# OSC4ReTHM.net
KiCad netlist of a schematic drawn in EAGLE
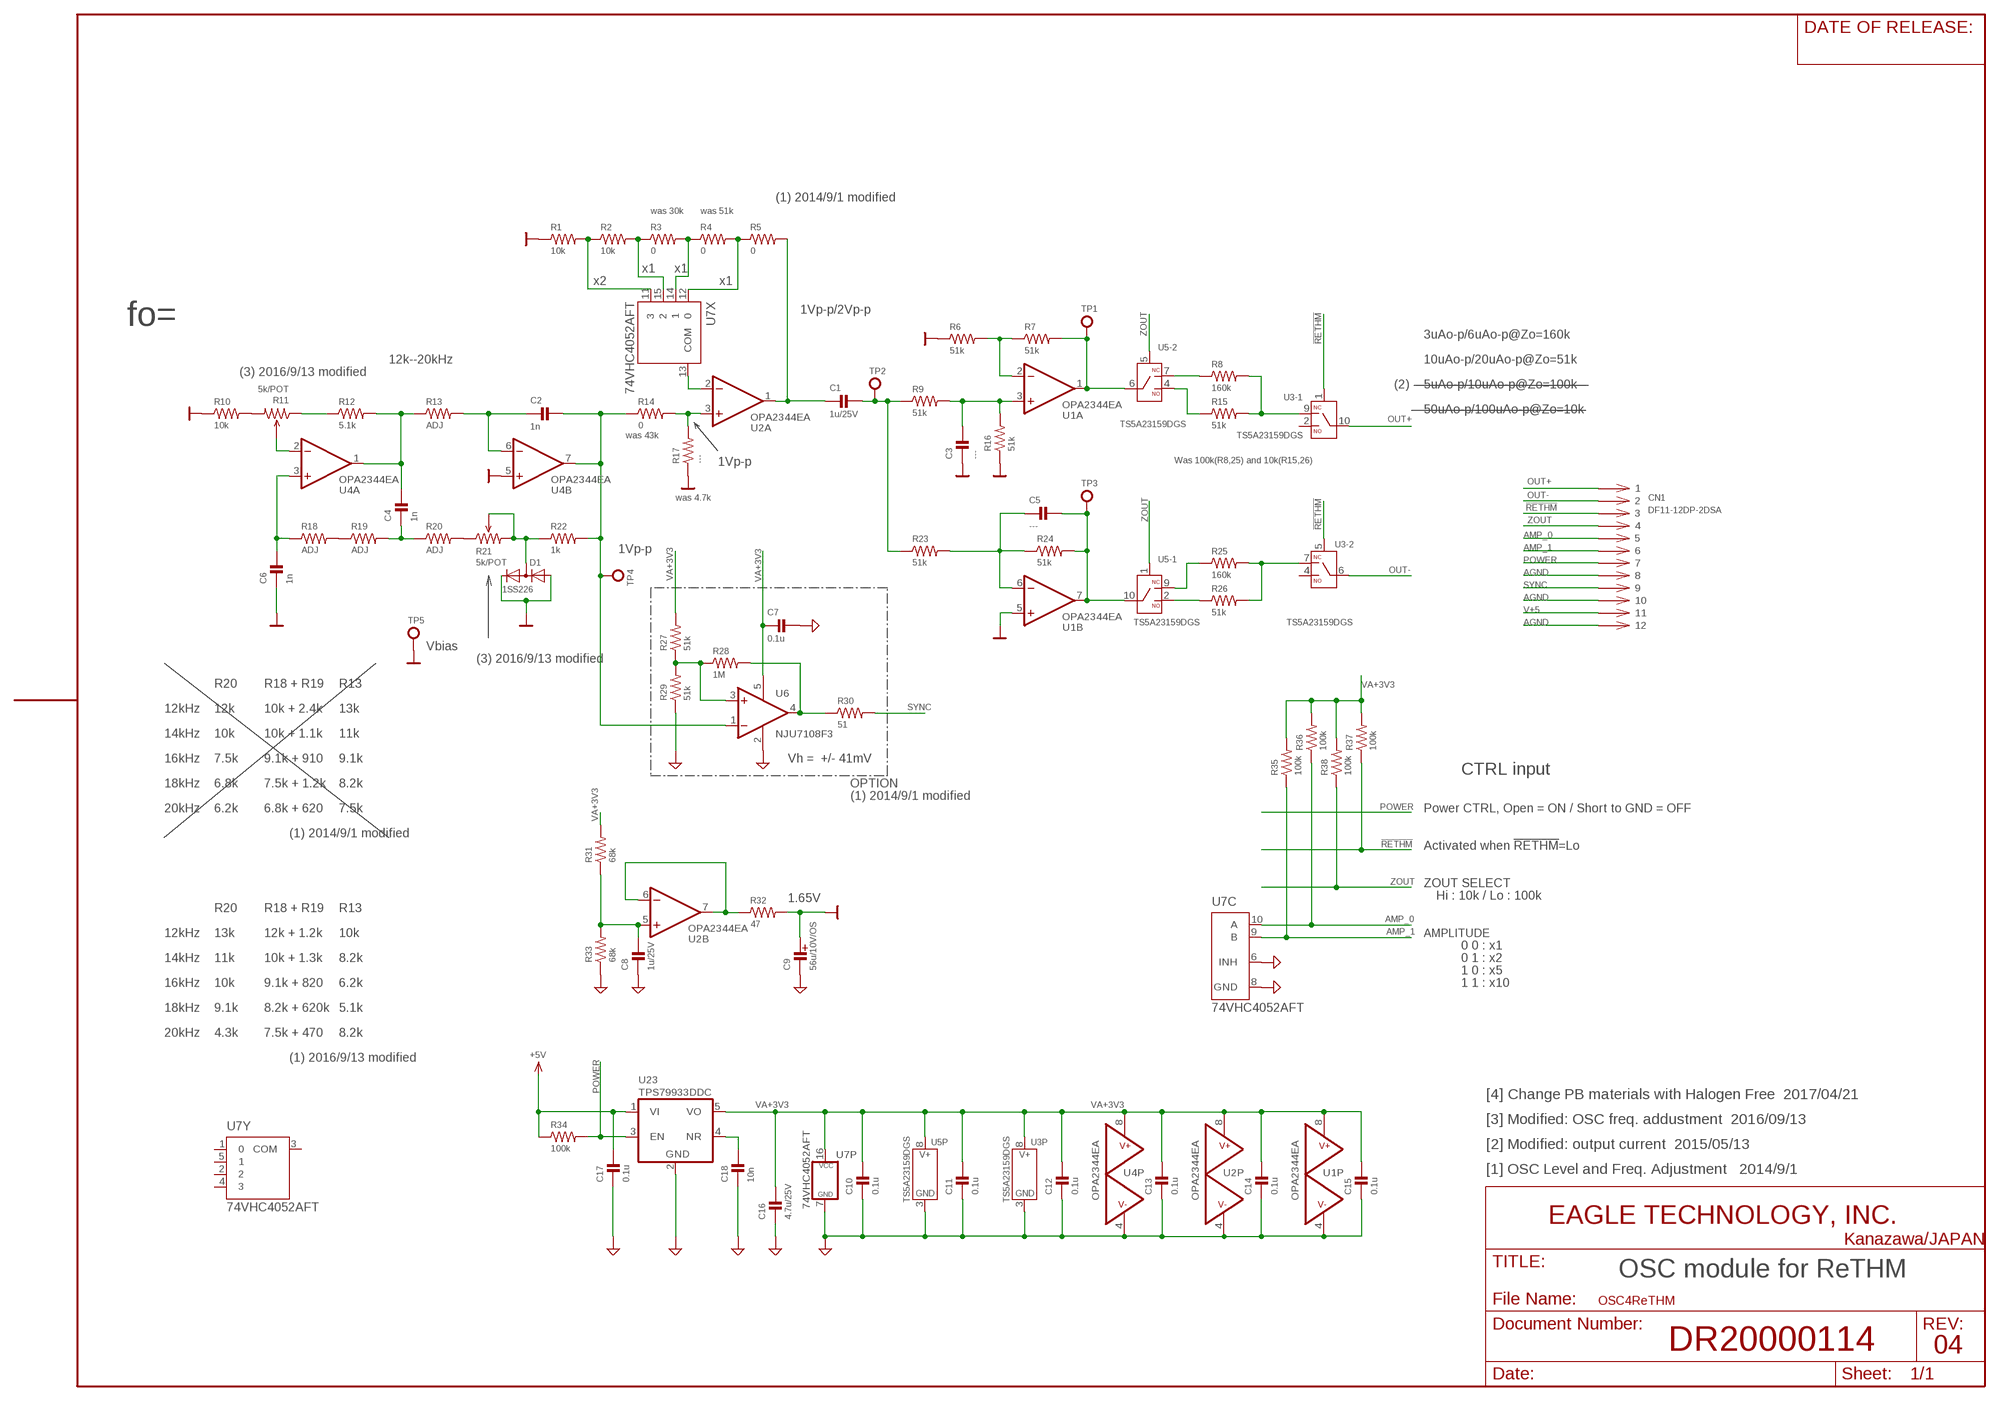
[diagram p0: schematic, sheet 1]

(export (version "E")
  (design (tool "Eeschema 10.0.6"))
  (components
    (comp (ref "C1")
      (value "1u/25V")
      (footprint "eagle-import:CM1608")
      (libsource (lib "eagle-import") (part "CSMD1.6X0.8MM"))
    )
    (comp (ref "C2")
      (value "1n")
      (footprint "eagle-import:CM2012")
      (libsource (lib "eagle-import") (part "CSMD2.0X1.2MM"))
    )
    (comp (ref "C3")
      (value "---")
      (footprint "eagle-import:CM2012")
      (libsource (lib "eagle-import") (part "CSMD2.0X1.2MM"))
    )
    (comp (ref "C4")
      (value "1n")
      (footprint "eagle-import:CM2012")
      (libsource (lib "eagle-import") (part "CSMD2.0X1.2MM"))
    )
    (comp (ref "C5")
      (value "---")
      (footprint "eagle-import:CM2012")
      (libsource (lib "eagle-import") (part "CSMD2.0X1.2MM"))
    )
    (comp (ref "C6")
      (value "1n")
      (footprint "eagle-import:CM2012")
      (libsource (lib "eagle-import") (part "CSMD2.0X1.2MM"))
    )
    (comp (ref "C7")
      (value "0.1u")
      (footprint "eagle-import:CM1608")
      (libsource (lib "eagle-import") (part "CSMD1.6X0.8MM"))
    )
    (comp (ref "C8")
      (value "1u/25V")
      (footprint "eagle-import:CM1608")
      (libsource (lib "eagle-import") (part "CSMD1.6X0.8MM"))
    )
    (comp (ref "C9")
      (value "56u/10V/OS")
      (footprint "eagle-import:PHI_6.3")
      (libsource (lib "eagle-import") (part "C_POL6.3-2.5MM"))
    )
    (comp (ref "C10")
      (value "0.1u")
      (footprint "eagle-import:CM1608")
      (libsource (lib "eagle-import") (part "CSMD1.6X0.8MM"))
    )
    (comp (ref "C11")
      (value "0.1u")
      (footprint "eagle-import:CM1608")
      (libsource (lib "eagle-import") (part "CSMD1.6X0.8MM"))
    )
    (comp (ref "C12")
      (value "0.1u")
      (footprint "eagle-import:CM1608")
      (libsource (lib "eagle-import") (part "CSMD1.6X0.8MM"))
    )
    (comp (ref "C13")
      (value "0.1u")
      (footprint "eagle-import:CM1608")
      (libsource (lib "eagle-import") (part "CSMD1.6X0.8MM"))
    )
    (comp (ref "C14")
      (value "0.1u")
      (footprint "eagle-import:CM1608")
      (libsource (lib "eagle-import") (part "CSMD1.6X0.8MM"))
    )
    (comp (ref "C15")
      (value "0.1u")
      (footprint "eagle-import:CM1608")
      (libsource (lib "eagle-import") (part "CSMD1.6X0.8MM"))
    )
    (comp (ref "C16")
      (value "4.7u/25V")
      (footprint "eagle-import:CM2012")
      (libsource (lib "eagle-import") (part "CSMD2.0X1.2MM"))
    )
    (comp (ref "C17")
      (value "0.1u")
      (footprint "eagle-import:CM1608")
      (libsource (lib "eagle-import") (part "CSMD1.6X0.8MM"))
    )
    (comp (ref "C18")
      (value "10n")
      (footprint "eagle-import:CM2012")
      (libsource (lib "eagle-import") (part "CSMD2.0X1.2MM"))
    )
    (comp (ref "CN1")
      (value "DF11-12DP-2DSA")
      (footprint "eagle-import:DF11-12DP-2DSA")
      (libsource (lib "eagle-import") (part "DF11-12DP-2DSA"))
    )
    (comp (ref "D1")
      (value "1SS226")
      (footprint "eagle-import:SOT23")
      (libsource (lib "eagle-import") (part "1SS226"))
    )
    (comp (ref "R1")
      (value "10k")
      (footprint "eagle-import:RM1608")
      (libsource (lib "eagle-import") (part "RSMD1.6X0.8MM"))
    )
    (comp (ref "R2")
      (value "10k")
      (footprint "eagle-import:RM1608")
      (libsource (lib "eagle-import") (part "RSMD1.6X0.8MM"))
    )
    (comp (ref "R3")
      (value "0")
      (footprint "eagle-import:RM1608")
      (libsource (lib "eagle-import") (part "RSMD1.6X0.8MM"))
    )
    (comp (ref "R4")
      (value "0")
      (footprint "eagle-import:RM1608")
      (libsource (lib "eagle-import") (part "RSMD1.6X0.8MM"))
    )
    (comp (ref "R5")
      (value "0")
      (footprint "eagle-import:RM1608")
      (libsource (lib "eagle-import") (part "RSMD1.6X0.8MM"))
    )
    (comp (ref "R6")
      (value "51k")
      (footprint "eagle-import:RM1608")
      (libsource (lib "eagle-import") (part "RSMD1.6X0.8MM"))
    )
    (comp (ref "R7")
      (value "51k")
      (footprint "eagle-import:RM1608")
      (libsource (lib "eagle-import") (part "RSMD1.6X0.8MM"))
    )
    (comp (ref "R8")
      (value "160k")
      (footprint "eagle-import:RM1608")
      (libsource (lib "eagle-import") (part "RSMD1.6X0.8MM"))
    )
    (comp (ref "R9")
      (value "51k")
      (footprint "eagle-import:RM1608")
      (libsource (lib "eagle-import") (part "RSMD1.6X0.8MM"))
    )
    (comp (ref "R10")
      (value "10k")
      (footprint "eagle-import:RM1608")
      (libsource (lib "eagle-import") (part "RSMD1.6X0.8MM"))
    )
    (comp (ref "R11")
      (value "5k/POT")
      (footprint "eagle-import:CT-6")
      (libsource (lib "eagle-import") (part "R_POT"))
    )
    (comp (ref "R12")
      (value "5.1k")
      (footprint "eagle-import:RM1608")
      (libsource (lib "eagle-import") (part "RSMD1.6X0.8MM"))
    )
    (comp (ref "R13")
      (value "ADJ")
      (footprint "eagle-import:RM1608")
      (libsource (lib "eagle-import") (part "RSMD1.6X0.8MM"))
    )
    (comp (ref "R14")
      (value "0")
      (footprint "eagle-import:RM1608")
      (libsource (lib "eagle-import") (part "RSMD1.6X0.8MM"))
    )
    (comp (ref "R15")
      (value "51k")
      (footprint "eagle-import:RM1608")
      (libsource (lib "eagle-import") (part "RSMD1.6X0.8MM"))
    )
    (comp (ref "R16")
      (value "51k")
      (footprint "eagle-import:RM1608")
      (libsource (lib "eagle-import") (part "RSMD1.6X0.8MM"))
    )
    (comp (ref "R17")
      (value "---")
      (footprint "eagle-import:RM1608")
      (libsource (lib "eagle-import") (part "RSMD1.6X0.8MM"))
    )
    (comp (ref "R18")
      (value "ADJ")
      (footprint "eagle-import:RM1608")
      (libsource (lib "eagle-import") (part "RSMD1.6X0.8MM"))
    )
    (comp (ref "R19")
      (value "ADJ")
      (footprint "eagle-import:RM1608")
      (libsource (lib "eagle-import") (part "RSMD1.6X0.8MM"))
    )
    (comp (ref "R20")
      (value "ADJ")
      (footprint "eagle-import:RM1608")
      (libsource (lib "eagle-import") (part "RSMD1.6X0.8MM"))
    )
    (comp (ref "R21")
      (value "5k/POT")
      (footprint "eagle-import:CT-6")
      (libsource (lib "eagle-import") (part "R_POT"))
    )
    (comp (ref "R22")
      (value "1k")
      (footprint "eagle-import:RM1608")
      (libsource (lib "eagle-import") (part "RSMD1.6X0.8MM"))
    )
    (comp (ref "R23")
      (value "51k")
      (footprint "eagle-import:RM1608")
      (libsource (lib "eagle-import") (part "RSMD1.6X0.8MM"))
    )
    (comp (ref "R24")
      (value "51k")
      (footprint "eagle-import:RM1608")
      (libsource (lib "eagle-import") (part "RSMD1.6X0.8MM"))
    )
    (comp (ref "R25")
      (value "160k")
      (footprint "eagle-import:RM1608")
      (libsource (lib "eagle-import") (part "RSMD1.6X0.8MM"))
    )
    (comp (ref "R26")
      (value "51k")
      (footprint "eagle-import:RM1608")
      (libsource (lib "eagle-import") (part "RSMD1.6X0.8MM"))
    )
    (comp (ref "R27")
      (value "51k")
      (footprint "eagle-import:RM1608")
      (libsource (lib "eagle-import") (part "RSMD1.6X0.8MM"))
    )
    (comp (ref "R28")
      (value "1M")
      (footprint "eagle-import:RM1608")
      (libsource (lib "eagle-import") (part "RSMD1.6X0.8MM"))
    )
    (comp (ref "R29")
      (value "51k")
      (footprint "eagle-import:RM1608")
      (libsource (lib "eagle-import") (part "RSMD1.6X0.8MM"))
    )
    (comp (ref "R30")
      (value "51")
      (footprint "eagle-import:RM1608")
      (libsource (lib "eagle-import") (part "RSMD1.6X0.8MM"))
    )
    (comp (ref "R31")
      (value "68k")
      (footprint "eagle-import:RM1608")
      (libsource (lib "eagle-import") (part "RSMD1.6X0.8MM"))
    )
    (comp (ref "R32")
      (value "47")
      (footprint "eagle-import:RM1608")
      (libsource (lib "eagle-import") (part "RSMD1.6X0.8MM"))
    )
    (comp (ref "R33")
      (value "68k")
      (footprint "eagle-import:RM1608")
      (libsource (lib "eagle-import") (part "RSMD1.6X0.8MM"))
    )
    (comp (ref "R34")
      (value "100k")
      (footprint "eagle-import:RM1608")
      (libsource (lib "eagle-import") (part "RSMD1.6X0.8MM"))
    )
    (comp (ref "R35")
      (value "100k")
      (footprint "eagle-import:RM1608")
      (libsource (lib "eagle-import") (part "RSMD1.6X0.8MM"))
    )
    (comp (ref "R36")
      (value "100k")
      (footprint "eagle-import:RM1608")
      (libsource (lib "eagle-import") (part "RSMD1.6X0.8MM"))
    )
    (comp (ref "R37")
      (value "100k")
      (footprint "eagle-import:RM1608")
      (libsource (lib "eagle-import") (part "RSMD1.6X0.8MM"))
    )
    (comp (ref "R38")
      (value "100k")
      (footprint "eagle-import:RM1608")
      (libsource (lib "eagle-import") (part "RSMD1.6X0.8MM"))
    )
    (comp (ref "TP1")
      (value "TP-1PAD")
      (footprint "eagle-import:TP_PAD_1MM")
      (libsource (lib "eagle-import") (part "TP-1PAD"))
    )
    (comp (ref "TP2")
      (value "TP-LC3G")
      (footprint "eagle-import:TP_TH_0R9MM")
      (libsource (lib "eagle-import") (part "TP-LC3G"))
    )
    (comp (ref "TP3")
      (value "TP-1PAD")
      (footprint "eagle-import:TP_PAD_1MM")
      (libsource (lib "eagle-import") (part "TP-1PAD"))
    )
    (comp (ref "TP4")
      (value "TP-LC3G")
      (footprint "eagle-import:TP_TH_0R9MM")
      (libsource (lib "eagle-import") (part "TP-LC3G"))
    )
    (comp (ref "TP5")
      (value "TP-1PAD")
      (footprint "eagle-import:TP_PAD_1MM")
      (libsource (lib "eagle-import") (part "TP-1PAD"))
    )
    (comp (ref "U1")
      (value "OPA2344EA")
      (footprint "eagle-import:MSO8_AEL")
      (libsource (lib "eagle-import") (part "OPA2344DGK"))
    )
    (comp (ref "U2")
      (value "OPA2344EA")
      (footprint "eagle-import:MSO8_AEL")
      (libsource (lib "eagle-import") (part "OPA2344DGK"))
    )
    (comp (ref "U3")
      (value "TS5A23159DGS")
      (footprint "eagle-import:MSOP10")
      (libsource (lib "eagle-import") (part "TS5A23159DGS"))
    )
    (comp (ref "U4")
      (value "OPA2344EA")
      (footprint "eagle-import:MSO8_AEL")
      (libsource (lib "eagle-import") (part "OPA2344DGK"))
    )
    (comp (ref "U5")
      (value "TS5A23159DGS")
      (footprint "eagle-import:MSOP10")
      (libsource (lib "eagle-import") (part "TS5A23159DGS"))
    )
    (comp (ref "U6")
      (value "NJU7108F3")
      (footprint "eagle-import:SC88A")
      (libsource (lib "eagle-import") (part "NJU7108F3"))
    )
    (comp (ref "U7")
      (value "74VHC4052AFT")
      (footprint "eagle-import:TSSOP16-P-044-065A")
      (libsource (lib "eagle-import") (part "744052AFTVHC"))
    )
    (comp (ref "U23")
      (value "TPS79933DDC")
      (footprint "eagle-import:SOT-23-5")
      (libsource (lib "eagle-import") (part "TPS799DDC33"))
    )
  )
  (nets
    (net (code "1") (name "/AMP_0") (class "Default")
      (node (ref "CN1") (pin "5") (pinfunction "5_5") (pintype "bidirectional"))
      (node (ref "R36") (pin "1") (pinfunction "1_1") (pintype "passive"))
      (node (ref "U7") (pin "10") (pinfunction "A_10") (pintype "input"))
    )
    (net (code "2") (name "/AMP_1") (class "Default")
      (node (ref "CN1") (pin "6") (pinfunction "6_6") (pintype "bidirectional"))
      (node (ref "R35") (pin "1") (pinfunction "1_1") (pintype "passive"))
      (node (ref "U7") (pin "9") (pinfunction "B_9") (pintype "input"))
    )
    (net (code "3") (name "/OUT+") (class "Default")
      (node (ref "CN1") (pin "1") (pinfunction "1_1") (pintype "bidirectional"))
      (node (ref "U3") (pin "10") (pinfunction "COM_10") (pintype "bidirectional"))
    )
    (net (code "4") (name "/OUT-") (class "Default")
      (node (ref "CN1") (pin "2") (pinfunction "2_2") (pintype "bidirectional"))
      (node (ref "U3") (pin "6") (pinfunction "COM_6") (pintype "bidirectional"))
    )
    (net (code "5") (name "/POWER") (class "Default")
      (node (ref "CN1") (pin "7") (pinfunction "7_7") (pintype "bidirectional"))
      (node (ref "R34") (pin "2") (pinfunction "2_2") (pintype "passive"))
      (node (ref "U23") (pin "3") (pinfunction "EN_3") (pintype "input"))
    )
    (net (code "6") (name "/SYNC") (class "Default")
      (node (ref "CN1") (pin "9") (pinfunction "9_9") (pintype "bidirectional"))
      (node (ref "R30") (pin "2") (pinfunction "2_2") (pintype "passive"))
    )
    (net (code "7") (name "/VA+3V3") (class "Default")
      (node (ref "C10") (pin "1") (pinfunction "1_1") (pintype "passive"))
      (node (ref "C11") (pin "1") (pinfunction "1_1") (pintype "passive"))
      (node (ref "C12") (pin "1") (pinfunction "1_1") (pintype "passive"))
      (node (ref "C13") (pin "1") (pinfunction "1_1") (pintype "passive"))
      (node (ref "C14") (pin "1") (pinfunction "1_1") (pintype "passive"))
      (node (ref "C15") (pin "1") (pinfunction "1_1") (pintype "passive"))
      (node (ref "C16") (pin "1") (pinfunction "1_1") (pintype "passive"))
      (node (ref "C7") (pin "2") (pinfunction "2_2") (pintype "passive"))
      (node (ref "R27") (pin "2") (pinfunction "2_2") (pintype "passive"))
      (node (ref "R31") (pin "2") (pinfunction "2_2") (pintype "passive"))
      (node (ref "R35") (pin "2") (pinfunction "2_2") (pintype "passive"))
      (node (ref "R36") (pin "2") (pinfunction "2_2") (pintype "passive"))
      (node (ref "R37") (pin "2") (pinfunction "2_2") (pintype "passive"))
      (node (ref "R38") (pin "2") (pinfunction "2_2") (pintype "passive"))
      (node (ref "U1") (pin "8") (pinfunction "V+_8") (pintype "power_in"))
      (node (ref "U2") (pin "8") (pinfunction "V+_8") (pintype "power_in"))
      (node (ref "U23") (pin "5") (pinfunction "VO_5") (pintype "passive"))
      (node (ref "U3") (pin "8") (pinfunction "V+_8") (pintype "power_in"))
      (node (ref "U4") (pin "8") (pinfunction "V+_8") (pintype "power_in"))
      (node (ref "U5") (pin "8") (pinfunction "V+_8") (pintype "power_in"))
      (node (ref "U6") (pin "5") (pinfunction "V+_5") (pintype "power_in"))
      (node (ref "U7") (pin "16") (pinfunction "VCC_16") (pintype "power_in"))
    )
    (net (code "8") (name "/ZOUT") (class "Default")
      (node (ref "CN1") (pin "4") (pinfunction "4_4") (pintype "bidirectional"))
      (node (ref "R38") (pin "1") (pinfunction "1_1") (pintype "passive"))
      (node (ref "U5") (pin "1") (pinfunction "IN_1") (pintype "input"))
      (node (ref "U5") (pin "5") (pinfunction "IN_5") (pintype "input"))
    )
    (net (code "9") (name "/~{RETHM}") (class "Default")
      (node (ref "CN1") (pin "3") (pinfunction "3_3") (pintype "bidirectional"))
      (node (ref "R37") (pin "1") (pinfunction "1_1") (pintype "passive"))
      (node (ref "U3") (pin "1") (pinfunction "IN_1") (pintype "input"))
      (node (ref "U3") (pin "5") (pinfunction "IN_5") (pintype "input"))
    )
    (net (code "10") (name "0V") (class "Default")
      (node (ref "C3") (pin "2") (pinfunction "2_2") (pintype "passive"))
      (node (ref "C6") (pin "2") (pinfunction "2_2") (pintype "passive"))
      (node (ref "C9") (pin "POS") (pinfunction "POS_POS") (pintype "passive"))
      (node (ref "D1") (pin "1") (pinfunction "A_1") (pintype "passive"))
      (node (ref "D1") (pin "2") (pinfunction "C_2") (pintype "passive"))
      (node (ref "R1") (pin "1") (pinfunction "1_1") (pintype "passive"))
      (node (ref "R10") (pin "1") (pinfunction "1_1") (pintype "passive"))
      (node (ref "R16") (pin "1") (pinfunction "1_1") (pintype "passive"))
      (node (ref "R17") (pin "1") (pinfunction "1_1") (pintype "passive"))
      (node (ref "R32") (pin "2") (pinfunction "2_2") (pintype "passive"))
      (node (ref "R6") (pin "1") (pinfunction "1_1") (pintype "passive"))
      (node (ref "TP5") (pin "P$1") (pinfunction "MP_P$1") (pintype "passive"))
      (node (ref "U1") (pin "5") (pinfunction "+IN_5") (pintype "input"))
      (node (ref "U4") (pin "5") (pinfunction "+IN_5") (pintype "input"))
    )
    (net (code "11") (name "AGND") (class "Default")
      (node (ref "C10") (pin "2") (pinfunction "2_2") (pintype "passive"))
      (node (ref "C11") (pin "2") (pinfunction "2_2") (pintype "passive"))
      (node (ref "C12") (pin "2") (pinfunction "2_2") (pintype "passive"))
      (node (ref "C13") (pin "2") (pinfunction "2_2") (pintype "passive"))
      (node (ref "C14") (pin "2") (pinfunction "2_2") (pintype "passive"))
      (node (ref "C15") (pin "2") (pinfunction "2_2") (pintype "passive"))
      (node (ref "C16") (pin "2") (pinfunction "2_2") (pintype "passive"))
      (node (ref "C17") (pin "2") (pinfunction "2_2") (pintype "passive"))
      (node (ref "C18") (pin "2") (pinfunction "2_2") (pintype "passive"))
      (node (ref "C7") (pin "1") (pinfunction "1_1") (pintype "passive"))
      (node (ref "C8") (pin "2") (pinfunction "2_2") (pintype "passive"))
      (node (ref "C9") (pin "NEG") (pinfunction "NEG_NEG") (pintype "passive"))
      (node (ref "CN1") (pin "10") (pinfunction "10_10") (pintype "bidirectional"))
      (node (ref "CN1") (pin "12") (pinfunction "12_12") (pintype "bidirectional"))
      (node (ref "CN1") (pin "8") (pinfunction "8_8") (pintype "bidirectional"))
      (node (ref "R29") (pin "1") (pinfunction "1_1") (pintype "passive"))
      (node (ref "R33") (pin "1") (pinfunction "1_1") (pintype "passive"))
      (node (ref "U1") (pin "4") (pinfunction "V-_4") (pintype "power_in"))
      (node (ref "U2") (pin "4") (pinfunction "V-_4") (pintype "power_in"))
      (node (ref "U23") (pin "2") (pinfunction "GND_2") (pintype "passive"))
      (node (ref "U3") (pin "3") (pinfunction "V-_3") (pintype "power_in"))
      (node (ref "U4") (pin "4") (pinfunction "V-_4") (pintype "power_in"))
      (node (ref "U5") (pin "3") (pinfunction "V-_3") (pintype "power_in"))
      (node (ref "U6") (pin "2") (pinfunction "V-_2") (pintype "power_in"))
      (node (ref "U7") (pin "6") (pinfunction "INH_6") (pintype "input"))
      (node (ref "U7") (pin "7") (pinfunction "GND_7") (pintype "power_in"))
      (node (ref "U7") (pin "8") (pinfunction "GND_8") (pintype "input"))
    )
    (net (code "12") (name "Net-(C4-Pad2)") (class "Default")
      (node (ref "C4") (pin "2") (pinfunction "2_2") (pintype "passive"))
      (node (ref "R19") (pin "2") (pinfunction "2_2") (pintype "passive"))
      (node (ref "R20") (pin "1") (pinfunction "1_1") (pintype "passive"))
    )
    (net (code "13") (name "Net-(D1-AC)") (class "Default")
      (node (ref "D1") (pin "3") (pinfunction "AC_3") (pintype "passive"))
      (node (ref "R21") (pin "2") (pinfunction "2_2") (pintype "passive"))
      (node (ref "R21") (pin "3") (pinfunction "3_3") (pintype "passive"))
      (node (ref "R22") (pin "1") (pinfunction "1_1") (pintype "passive"))
    )
    (net (code "14") (name "Net-(R10-Pad2)") (class "Default")
      (node (ref "R10") (pin "2") (pinfunction "2_2") (pintype "passive"))
      (node (ref "R11") (pin "3") (pinfunction "3_3") (pintype "passive"))
    )
    (net (code "15") (name "Net-(R11-Pad1)") (class "Default")
      (node (ref "R11") (pin "1") (pinfunction "1_1") (pintype "passive"))
      (node (ref "R12") (pin "1") (pinfunction "1_1") (pintype "passive"))
    )
    (net (code "16") (name "Net-(R18-Pad2)") (class "Default")
      (node (ref "R18") (pin "2") (pinfunction "2_2") (pintype "passive"))
      (node (ref "R19") (pin "1") (pinfunction "1_1") (pintype "passive"))
    )
    (net (code "17") (name "Net-(R20-Pad2)") (class "Default")
      (node (ref "R20") (pin "2") (pinfunction "2_2") (pintype "passive"))
      (node (ref "R21") (pin "1") (pinfunction "1_1") (pintype "passive"))
    )
    (net (code "18") (name "Net-(TP1-MP)") (class "Default")
      (node (ref "R7") (pin "2") (pinfunction "2_2") (pintype "passive"))
      (node (ref "TP1") (pin "P$1") (pinfunction "MP_P$1") (pintype "passive"))
      (node (ref "U1") (pin "1") (pinfunction "OUT_1") (pintype "output"))
      (node (ref "U5") (pin "6") (pinfunction "COM_6") (pintype "bidirectional"))
    )
    (net (code "19") (name "Net-(TP2-MP)") (class "Default")
      (node (ref "C1") (pin "1") (pinfunction "1_1") (pintype "passive"))
      (node (ref "R23") (pin "1") (pinfunction "1_1") (pintype "passive"))
      (node (ref "R9") (pin "1") (pinfunction "1_1") (pintype "passive"))
      (node (ref "TP2") (pin "1") (pinfunction "MP_1") (pintype "passive"))
    )
    (net (code "20") (name "Net-(TP3-MP)") (class "Default")
      (node (ref "C5") (pin "1") (pinfunction "1_1") (pintype "passive"))
      (node (ref "R24") (pin "2") (pinfunction "2_2") (pintype "passive"))
      (node (ref "TP3") (pin "P$1") (pinfunction "MP_P$1") (pintype "passive"))
      (node (ref "U1") (pin "7") (pinfunction "OUT_7") (pintype "output"))
      (node (ref "U5") (pin "10") (pinfunction "COM_10") (pintype "bidirectional"))
    )
    (net (code "21") (name "Net-(TP4-MP)") (class "Default")
      (node (ref "C2") (pin "1") (pinfunction "1_1") (pintype "passive"))
      (node (ref "R14") (pin "1") (pinfunction "1_1") (pintype "passive"))
      (node (ref "R22") (pin "2") (pinfunction "2_2") (pintype "passive"))
      (node (ref "TP4") (pin "1") (pinfunction "MP_1") (pintype "passive"))
      (node (ref "U4") (pin "7") (pinfunction "OUT_7") (pintype "output"))
      (node (ref "U6") (pin "1") (pinfunction "-IN_1") (pintype "input"))
    )
    (net (code "22") (name "Net-(U1A-+IN)") (class "Default")
      (node (ref "C3") (pin "1") (pinfunction "1_1") (pintype "passive"))
      (node (ref "R16") (pin "2") (pinfunction "2_2") (pintype "passive"))
      (node (ref "R9") (pin "2") (pinfunction "2_2") (pintype "passive"))
      (node (ref "U1") (pin "3") (pinfunction "+IN_3") (pintype "input"))
    )
    (net (code "23") (name "Net-(U1A--IN)") (class "Default")
      (node (ref "R6") (pin "2") (pinfunction "2_2") (pintype "passive"))
      (node (ref "R7") (pin "1") (pinfunction "1_1") (pintype "passive"))
      (node (ref "U1") (pin "2") (pinfunction "-IN_2") (pintype "input"))
    )
    (net (code "24") (name "Net-(U1B--IN)") (class "Default")
      (node (ref "C5") (pin "2") (pinfunction "2_2") (pintype "passive"))
      (node (ref "R23") (pin "2") (pinfunction "2_2") (pintype "passive"))
      (node (ref "R24") (pin "1") (pinfunction "1_1") (pintype "passive"))
      (node (ref "U1") (pin "6") (pinfunction "-IN_6") (pintype "input"))
    )
    (net (code "25") (name "Net-(U2A-+IN)") (class "Default")
      (node (ref "R14") (pin "2") (pinfunction "2_2") (pintype "passive"))
      (node (ref "R17") (pin "2") (pinfunction "2_2") (pintype "passive"))
      (node (ref "U2") (pin "3") (pinfunction "+IN_3") (pintype "input"))
    )
    (net (code "26") (name "Net-(U2A--IN)") (class "Default")
      (node (ref "U2") (pin "2") (pinfunction "-IN_2") (pintype "input"))
      (node (ref "U7") (pin "13") (pinfunction "COM_13") (pintype "bidirectional"))
    )
    (net (code "27") (name "Net-(U2A-OUT)") (class "Default")
      (node (ref "C1") (pin "2") (pinfunction "2_2") (pintype "passive"))
      (node (ref "R5") (pin "2") (pinfunction "2_2") (pintype "passive"))
      (node (ref "U2") (pin "1") (pinfunction "OUT_1") (pintype "output"))
    )
    (net (code "28") (name "Net-(U2B-+IN)") (class "Default")
      (node (ref "C8") (pin "1") (pinfunction "1_1") (pintype "passive"))
      (node (ref "R31") (pin "1") (pinfunction "1_1") (pintype "passive"))
      (node (ref "R33") (pin "2") (pinfunction "2_2") (pintype "passive"))
      (node (ref "U2") (pin "5") (pinfunction "+IN_5") (pintype "input"))
    )
    (net (code "29") (name "Net-(U2B--IN)") (class "Default")
      (node (ref "R32") (pin "1") (pinfunction "1_1") (pintype "passive"))
      (node (ref "U2") (pin "6") (pinfunction "-IN_6") (pintype "input"))
      (node (ref "U2") (pin "7") (pinfunction "OUT_7") (pintype "output"))
    )
    (net (code "30") (name "Net-(U3A-NC)") (class "Default")
      (node (ref "R15") (pin "2") (pinfunction "2_2") (pintype "passive"))
      (node (ref "R8") (pin "2") (pinfunction "2_2") (pintype "passive"))
      (node (ref "U3") (pin "9") (pinfunction "NC_9") (pintype "bidirectional"))
    )
    (net (code "31") (name "Net-(U3B-NC)") (class "Default")
      (node (ref "R25") (pin "2") (pinfunction "2_2") (pintype "passive"))
      (node (ref "R26") (pin "2") (pinfunction "2_2") (pintype "passive"))
      (node (ref "U3") (pin "7") (pinfunction "NC_7") (pintype "bidirectional"))
    )
    (net (code "32") (name "Net-(U4A-+IN)") (class "Default")
      (node (ref "C6") (pin "1") (pinfunction "1_1") (pintype "passive"))
      (node (ref "R18") (pin "1") (pinfunction "1_1") (pintype "passive"))
      (node (ref "U4") (pin "3") (pinfunction "+IN_3") (pintype "input"))
    )
    (net (code "33") (name "Net-(U4A--IN)") (class "Default")
      (node (ref "R11") (pin "2") (pinfunction "2_2") (pintype "passive"))
      (node (ref "U4") (pin "2") (pinfunction "-IN_2") (pintype "input"))
    )
    (net (code "34") (name "Net-(U4A-OUT)") (class "Default")
      (node (ref "C4") (pin "1") (pinfunction "1_1") (pintype "passive"))
      (node (ref "R12") (pin "2") (pinfunction "2_2") (pintype "passive"))
      (node (ref "R13") (pin "1") (pinfunction "1_1") (pintype "passive"))
      (node (ref "U4") (pin "1") (pinfunction "OUT_1") (pintype "output"))
    )
    (net (code "35") (name "Net-(U4B--IN)") (class "Default")
      (node (ref "C2") (pin "2") (pinfunction "2_2") (pintype "passive"))
      (node (ref "R13") (pin "2") (pinfunction "2_2") (pintype "passive"))
      (node (ref "U4") (pin "6") (pinfunction "-IN_6") (pintype "input"))
    )
    (net (code "36") (name "Net-(U5A-NC)") (class "Default")
      (node (ref "R25") (pin "1") (pinfunction "1_1") (pintype "passive"))
      (node (ref "U5") (pin "9") (pinfunction "NC_9") (pintype "bidirectional"))
    )
    (net (code "37") (name "Net-(U5A-NO)") (class "Default")
      (node (ref "R26") (pin "1") (pinfunction "1_1") (pintype "passive"))
      (node (ref "U5") (pin "2") (pinfunction "NO_2") (pintype "bidirectional"))
    )
    (net (code "38") (name "Net-(U5B-NC)") (class "Default")
      (node (ref "R8") (pin "1") (pinfunction "1_1") (pintype "passive"))
      (node (ref "U5") (pin "7") (pinfunction "NC_7") (pintype "bidirectional"))
    )
    (net (code "39") (name "Net-(U5B-NO)") (class "Default")
      (node (ref "R15") (pin "1") (pinfunction "1_1") (pintype "passive"))
      (node (ref "U5") (pin "4") (pinfunction "NO_4") (pintype "bidirectional"))
    )
    (net (code "40") (name "Net-(U6-+IN)") (class "Default")
      (node (ref "R27") (pin "1") (pinfunction "1_1") (pintype "passive"))
      (node (ref "R28") (pin "1") (pinfunction "1_1") (pintype "passive"))
      (node (ref "R29") (pin "2") (pinfunction "2_2") (pintype "passive"))
      (node (ref "U6") (pin "3") (pinfunction "+IN_3") (pintype "input"))
    )
    (net (code "41") (name "Net-(U6-OUT)") (class "Default")
      (node (ref "R28") (pin "2") (pinfunction "2_2") (pintype "passive"))
      (node (ref "R30") (pin "1") (pinfunction "1_1") (pintype "passive"))
      (node (ref "U6") (pin "4") (pinfunction "OUT_4") (pintype "output"))
    )
    (net (code "42") (name "Net-(U7C-0)") (class "Default")
      (node (ref "R4") (pin "2") (pinfunction "2_2") (pintype "passive"))
      (node (ref "R5") (pin "1") (pinfunction "1_1") (pintype "passive"))
      (node (ref "U7") (pin "12") (pinfunction "0_12") (pintype "bidirectional"))
    )
    (net (code "43") (name "Net-(U7C-1)") (class "Default")
      (node (ref "R3") (pin "2") (pinfunction "2_2") (pintype "passive"))
      (node (ref "R4") (pin "1") (pinfunction "1_1") (pintype "passive"))
      (node (ref "U7") (pin "14") (pinfunction "1_14") (pintype "bidirectional"))
    )
    (net (code "44") (name "Net-(U7C-2)") (class "Default")
      (node (ref "R2") (pin "2") (pinfunction "2_2") (pintype "passive"))
      (node (ref "R3") (pin "1") (pinfunction "1_1") (pintype "passive"))
      (node (ref "U7") (pin "15") (pinfunction "2_15") (pintype "bidirectional"))
    )
    (net (code "45") (name "Net-(U7C-3)") (class "Default")
      (node (ref "R1") (pin "2") (pinfunction "2_2") (pintype "passive"))
      (node (ref "R2") (pin "1") (pinfunction "1_1") (pintype "passive"))
      (node (ref "U7") (pin "11") (pinfunction "3_11") (pintype "bidirectional"))
    )
    (net (code "46") (name "Net-(U23-NR)") (class "Default")
      (node (ref "C18") (pin "1") (pinfunction "1_1") (pintype "passive"))
      (node (ref "U23") (pin "4") (pinfunction "NR_4") (pintype "passive"))
    )
    (net (code "47") (name "V+5") (class "Default")
      (node (ref "C17") (pin "1") (pinfunction "1_1") (pintype "passive"))
      (node (ref "CN1") (pin "11") (pinfunction "11_11") (pintype "bidirectional"))
      (node (ref "R34") (pin "1") (pinfunction "1_1") (pintype "passive"))
      (node (ref "U23") (pin "1") (pinfunction "VI_1") (pintype "input"))
    )
    (net (code "48") (name "unconnected-(U3A-NO-Pad2)") (class "Default")
      (node (ref "U3") (pin "2") (pinfunction "NO_2") (pintype "bidirectional"))
    )
    (net (code "49") (name "unconnected-(U3B-NO-Pad4)") (class "Default")
      (node (ref "U3") (pin "4") (pinfunction "NO_4") (pintype "bidirectional"))
    )
    (net (code "50") (name "unconnected-(U7-Pad2)") (class "Default")
      (node (ref "U7") (pin "2") (pinfunction "2_2") (pintype "bidirectional"))
    )
    (net (code "51") (name "unconnected-(U7D-0-Pad1)") (class "Default")
      (node (ref "U7") (pin "1") (pinfunction "0_1") (pintype "bidirectional"))
    )
    (net (code "52") (name "unconnected-(U7D-1-Pad5)") (class "Default")
      (node (ref "U7") (pin "5") (pinfunction "1_5") (pintype "bidirectional"))
    )
    (net (code "53") (name "unconnected-(U7D-3-Pad4)") (class "Default")
      (node (ref "U7") (pin "4") (pinfunction "3_4") (pintype "bidirectional"))
    )
    (net (code "54") (name "unconnected-(U7D-COM-Pad3)") (class "Default")
      (node (ref "U7") (pin "3") (pinfunction "COM_3") (pintype "bidirectional"))
    )
  )
)
